# Copy_of_Plant_Monitor.net
KiCad netlist of a schematic drawn in Altium Designer
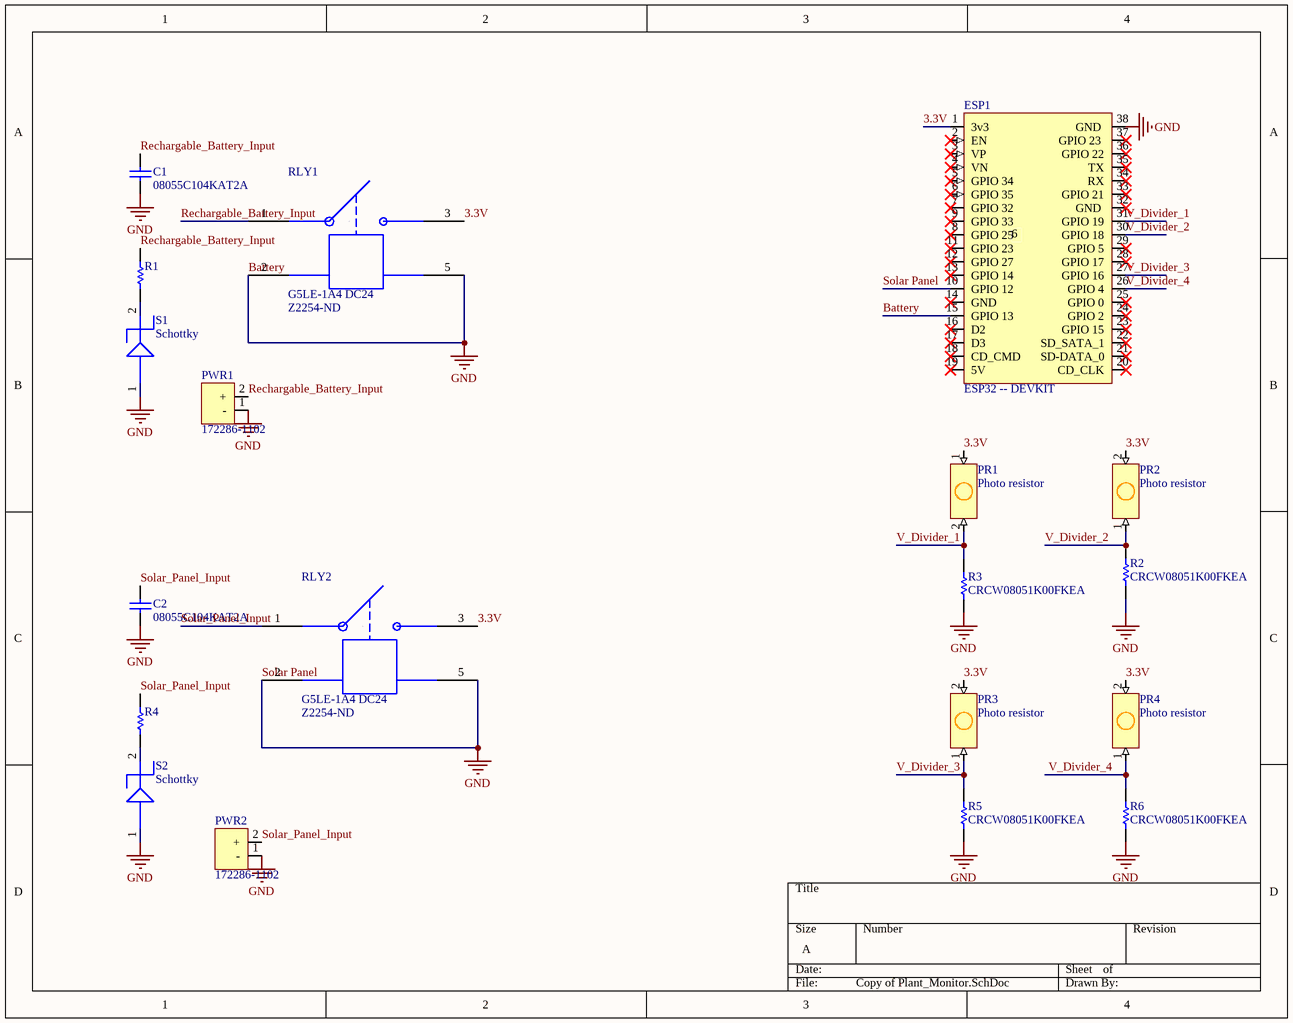
[diagram p0: Copy of Plant_Monitor.SchDoc]

(export (version "E")
  (design (tool "Eeschema 10.0.6"))
  (components
    (comp (ref "C1")
      (value "08055C104KAT2A")
      (footprint "R0805")
      (description "Chip Capacitor, Ceramic, 0.1 uF, 10%, 50 V, 0805, RoHS, Tape and Reel")
      (fields (field (name "MANUFACTURER") "AVX"))
      (libsource (lib "Schlib1") (part "CAP-NP-2"))
    )
    (comp (ref "C2")
      (value "08055C104KAT2A")
      (footprint "R0805")
      (description "Chip Capacitor, Ceramic, 0.1 uF, 10%, 50 V, 0805, RoHS, Tape and Reel")
      (fields (field (name "MANUFACTURER") "AVX"))
      (libsource (lib "Schlib1") (part "CAP-NP-2"))
    )
    (comp (ref "ESP1")
      (value "ESP32 -- DEVKIT")
      (footprint "ESP32 -- DEVKITC")
      (libsource (lib "Schlib1") (part "ESP32 -- DEVKIT"))
    )
    (comp (ref "PR1")
      (value "Photo resistor")
      (footprint "Photoresistor")
      (libsource (lib "Schlib1") (part "Photo resistor"))
    )
    (comp (ref "PR2")
      (value "Photo resistor")
      (footprint "Photoresistor")
      (libsource (lib "") (part "Photo resistor_1"))
    )
    (comp (ref "PR3")
      (value "Photo resistor")
      (footprint "Photoresistor")
      (libsource (lib "") (part "Photo resistor_1"))
    )
    (comp (ref "PR4")
      (value "Photo resistor")
      (footprint "Photoresistor")
      (libsource (lib "") (part "Photo resistor_1"))
    )
    (comp (ref "PWR1")
      (value "172286-1102")
      (footprint "2x1")
      (description "MOLEX - 172286-1102. - CONNECTOR, HEADER, 2POS, 1ROW, 3.5MM")
      (libsource (lib "Schlib1") (part "2 Pin Connector"))
    )
    (comp (ref "PWR2")
      (value "172286-1102")
      (footprint "2x1")
      (description "MOLEX - 172286-1102. - CONNECTOR, HEADER, 2POS, 1ROW, 3.5MM")
      (libsource (lib "Schlib1") (part "2 Pin Connector"))
    )
    (comp (ref "R1")
      (value "CRCW08051K00FKEA")
      (footprint "RESC2013X50X30NL20T20")
      (fields (field (name "MANUFACTURER") "Vishay Dale"))
      (libsource (lib "Altium Content Vault") (part "RES"))
    )
    (comp (ref "R2")
      (value "CRCW08051K00FKEA")
      (footprint "RESC2013X50X30NL20T20")
      (fields (field (name "MANUFACTURER") "Vishay Dale"))
      (libsource (lib "Altium Content Vault") (part "RES"))
    )
    (comp (ref "R3")
      (value "CRCW08051K00FKEA")
      (footprint "RESC2013X50X30NL20T20")
      (fields (field (name "MANUFACTURER") "Vishay Dale"))
      (libsource (lib "Altium Content Vault") (part "RES"))
    )
    (comp (ref "R4")
      (value "CRCW08051K00FKEA")
      (footprint "RESC2013X50X30NL20T20")
      (fields (field (name "MANUFACTURER") "Vishay Dale"))
      (libsource (lib "Altium Content Vault") (part "RES"))
    )
    (comp (ref "R5")
      (value "CRCW08051K00FKEA")
      (footprint "RESC2013X50X30NL20T20")
      (fields (field (name "MANUFACTURER") "Vishay Dale"))
      (libsource (lib "Altium Content Vault") (part "RES"))
    )
    (comp (ref "R6")
      (value "CRCW08051K00FKEA")
      (footprint "RESC2013X50X30NL20T20")
      (fields (field (name "MANUFACTURER") "Vishay Dale"))
      (libsource (lib "Altium Content Vault") (part "RES"))
    )
    (comp (ref "RLY1")
      (value "G5LE-1A4 DC24")
      (footprint "24V RELAY")
      (fields (field (name "SUPPLIER PART NUMBER 1") "Z2254-ND"))
      (libsource (lib "Schlib1") (part "RELAY"))
    )
    (comp (ref "RLY2")
      (value "G5LE-1A4 DC24")
      (footprint "24V RELAY")
      (fields (field (name "SUPPLIER PART NUMBER 1") "Z2254-ND"))
      (libsource (lib "Schlib1") (part "RELAY"))
    )
    (comp (ref "S1")
      (value "Schottky")
      (footprint "SODFL100X40-2N")
      (libsource (lib "Schlib1") (part "Schottky"))
    )
    (comp (ref "S2")
      (value "Schottky")
      (footprint "SODFL100X40-2N")
      (libsource (lib "Schlib1") (part "Schottky"))
    )
  )
  (nets
    (net (code "1") (name "/3.3V") (class "Default")
      (node (ref "ESP1") (pin "1") (pinfunction "3v3_1") (pintype "power_in"))
      (node (ref "PR1") (pin "1") (pintype "input"))
      (node (ref "PR2") (pin "2") (pintype "input"))
      (node (ref "PR3") (pin "2") (pintype "input"))
      (node (ref "PR4") (pin "2") (pintype "input"))
    )
    (net (code "2") (name "/Rechargable_Battery_Input") (class "Default")
      (node (ref "C1") (pin "2") (pinfunction "2_2") (pintype "passive"))
      (node (ref "PWR1") (pin "2") (pinfunction "+_2") (pintype "power_in"))
      (node (ref "R1") (pin "2") (pinfunction "2_2") (pintype "passive"))
    )
    (net (code "3") (name "/Solar_Panel_Input") (class "Default")
      (node (ref "C2") (pin "2") (pinfunction "2_2") (pintype "passive"))
      (node (ref "PWR2") (pin "2") (pinfunction "+_2") (pintype "power_in"))
      (node (ref "R4") (pin "2") (pinfunction "2_2") (pintype "passive"))
    )
    (net (code "4") (name "/V_Divider_1") (class "Default")
      (node (ref "ESP1") (pin "31") (pinfunction "GPIO_19_31") (pintype "bidirectional"))
      (node (ref "PR1") (pin "2") (pintype "input"))
      (node (ref "R3") (pin "2") (pinfunction "2_2") (pintype "passive"))
    )
    (net (code "5") (name "/V_Divider_2") (class "Default")
      (node (ref "ESP1") (pin "30") (pinfunction "GPIO_18_30") (pintype "bidirectional"))
      (node (ref "PR2") (pin "1") (pintype "input"))
      (node (ref "R2") (pin "2") (pinfunction "2_2") (pintype "passive"))
    )
    (net (code "6") (name "/V_Divider_3") (class "Default")
      (node (ref "ESP1") (pin "27") (pinfunction "GPIO_16_27") (pintype "bidirectional"))
      (node (ref "PR3") (pin "1") (pintype "input"))
      (node (ref "R5") (pin "2") (pinfunction "2_2") (pintype "passive"))
    )
    (net (code "7") (name "/V_Divider_4") (class "Default")
      (node (ref "ESP1") (pin "26") (pinfunction "GPIO_4_26") (pintype "bidirectional"))
      (node (ref "PR4") (pin "1") (pintype "input"))
      (node (ref "R6") (pin "2") (pinfunction "2_2") (pintype "passive"))
    )
    (net (code "8") (name "GND") (class "Default")
      (node (ref "C1") (pin "1") (pinfunction "1_1") (pintype "passive"))
      (node (ref "C2") (pin "1") (pinfunction "1_1") (pintype "passive"))
      (node (ref "ESP1") (pin "10") (pinfunction "GPIO_12_10") (pintype "bidirectional"))
      (node (ref "ESP1") (pin "15") (pinfunction "GPIO_13_15") (pintype "bidirectional"))
      (node (ref "ESP1") (pin "38") (pinfunction "GND_38") (pintype "power_in"))
      (node (ref "PWR1") (pin "1") (pinfunction "-_1") (pintype "power_in"))
      (node (ref "PWR2") (pin "1") (pinfunction "-_1") (pintype "power_in"))
      (node (ref "R2") (pin "1") (pinfunction "1_1") (pintype "passive"))
      (node (ref "R3") (pin "1") (pinfunction "1_1") (pintype "passive"))
      (node (ref "R5") (pin "1") (pinfunction "1_1") (pintype "passive"))
      (node (ref "R6") (pin "1") (pinfunction "1_1") (pintype "passive"))
      (node (ref "S1") (pin "1") (pintype "passive"))
      (node (ref "S2") (pin "1") (pintype "passive"))
    )
    (net (code "9") (name "Net-(R1-Pad1)") (class "Default")
      (node (ref "R1") (pin "1") (pinfunction "1_1") (pintype "passive"))
      (node (ref "S1") (pin "2") (pintype "passive"))
    )
    (net (code "10") (name "Net-(R4-Pad1)") (class "Default")
      (node (ref "R4") (pin "1") (pinfunction "1_1") (pintype "passive"))
      (node (ref "S2") (pin "2") (pintype "passive"))
    )
    (net (code "11") (name "unconnected-(ESP1-5V-Pad19)") (class "Default")
      (node (ref "ESP1") (pin "19") (pinfunction "5V_19") (pintype "power_in+no_connect"))
    )
    (net (code "12") (name "unconnected-(ESP1-CD_CLK-Pad20)") (class "Default")
      (node (ref "ESP1") (pin "20") (pinfunction "CD_CLK_20") (pintype "bidirectional+no_connect"))
    )
    (net (code "13") (name "unconnected-(ESP1-CD_CMD-Pad18)") (class "Default")
      (node (ref "ESP1") (pin "18") (pinfunction "CD_CMD_18") (pintype "bidirectional+no_connect"))
    )
    (net (code "14") (name "unconnected-(ESP1-D2-Pad16)") (class "Default")
      (node (ref "ESP1") (pin "16") (pinfunction "D2_16") (pintype "bidirectional+no_connect"))
    )
    (net (code "15") (name "unconnected-(ESP1-D3-Pad17)") (class "Default")
      (node (ref "ESP1") (pin "17") (pinfunction "D3_17") (pintype "bidirectional+no_connect"))
    )
    (net (code "16") (name "unconnected-(ESP1-EN-Pad2)") (class "Default")
      (node (ref "ESP1") (pin "2") (pinfunction "EN_2") (pintype "input+no_connect"))
    )
    (net (code "17") (name "unconnected-(ESP1-GND-Pad14)") (class "Default")
      (node (ref "ESP1") (pin "14") (pinfunction "GND_14") (pintype "power_in+no_connect"))
    )
    (net (code "18") (name "unconnected-(ESP1-GND-Pad32)") (class "Default")
      (node (ref "ESP1") (pin "32") (pinfunction "GND_32") (pintype "power_in+no_connect"))
    )
    (net (code "19") (name "unconnected-(ESP1-GPIO_0-Pad25)") (class "Default")
      (node (ref "ESP1") (pin "25") (pinfunction "GPIO_0_25") (pintype "bidirectional+no_connect"))
    )
    (net (code "20") (name "unconnected-(ESP1-GPIO_2-Pad24)") (class "Default")
      (node (ref "ESP1") (pin "24") (pinfunction "GPIO_2_24") (pintype "bidirectional+no_connect"))
    )
    (net (code "21") (name "unconnected-(ESP1-GPIO_5-Pad29)") (class "Default")
      (node (ref "ESP1") (pin "29") (pinfunction "GPIO_5_29") (pintype "bidirectional+no_connect"))
    )
    (net (code "22") (name "unconnected-(ESP1-GPIO_14-Pad13)") (class "Default")
      (node (ref "ESP1") (pin "13") (pinfunction "GPIO_14_13") (pintype "bidirectional+no_connect"))
    )
    (net (code "23") (name "unconnected-(ESP1-GPIO_15-Pad23)") (class "Default")
      (node (ref "ESP1") (pin "23") (pinfunction "GPIO_15_23") (pintype "bidirectional+no_connect"))
    )
    (net (code "24") (name "unconnected-(ESP1-GPIO_17-Pad28)") (class "Default")
      (node (ref "ESP1") (pin "28") (pinfunction "GPIO_17_28") (pintype "bidirectional+no_connect"))
    )
    (net (code "25") (name "unconnected-(ESP1-GPIO_21-Pad33)") (class "Default")
      (node (ref "ESP1") (pin "33") (pinfunction "GPIO_21_33") (pintype "bidirectional+no_connect"))
    )
    (net (code "26") (name "unconnected-(ESP1-GPIO_22-Pad36)") (class "Default")
      (node (ref "ESP1") (pin "36") (pinfunction "GPIO_22_36") (pintype "bidirectional+no_connect"))
    )
    (net (code "27") (name "unconnected-(ESP1-GPIO_23-Pad11)") (class "Default")
      (node (ref "ESP1") (pin "11") (pinfunction "GPIO_23_11") (pintype "bidirectional+no_connect"))
    )
    (net (code "28") (name "unconnected-(ESP1-GPIO_23-Pad37)") (class "Default")
      (node (ref "ESP1") (pin "37") (pinfunction "GPIO_23_37") (pintype "bidirectional+no_connect"))
    )
    (net (code "29") (name "unconnected-(ESP1-GPIO_25-Pad8)") (class "Default")
      (node (ref "ESP1") (pin "8") (pinfunction "GPIO_25_8") (pintype "bidirectional+no_connect"))
    )
    (net (code "30") (name "unconnected-(ESP1-GPIO_27-Pad12)") (class "Default")
      (node (ref "ESP1") (pin "12") (pinfunction "GPIO_27_12") (pintype "bidirectional+no_connect"))
    )
    (net (code "31") (name "unconnected-(ESP1-GPIO_32-Pad7)") (class "Default")
      (node (ref "ESP1") (pin "7") (pinfunction "GPIO_32_7") (pintype "bidirectional+no_connect"))
    )
    (net (code "32") (name "unconnected-(ESP1-GPIO_33-Pad9)") (class "Default")
      (node (ref "ESP1") (pin "9") (pinfunction "GPIO_33_9") (pintype "bidirectional+no_connect"))
    )
    (net (code "33") (name "unconnected-(ESP1-GPIO_34-Pad5)") (class "Default")
      (node (ref "ESP1") (pin "5") (pinfunction "GPIO_34_5") (pintype "input+no_connect"))
    )
    (net (code "34") (name "unconnected-(ESP1-GPIO_35-Pad6)") (class "Default")
      (node (ref "ESP1") (pin "6") (pinfunction "GPIO_35_6") (pintype "input+no_connect"))
    )
    (net (code "35") (name "unconnected-(ESP1-RX-Pad34)") (class "Default")
      (node (ref "ESP1") (pin "34") (pinfunction "RX_34") (pintype "bidirectional+no_connect"))
    )
    (net (code "36") (name "unconnected-(ESP1-SD-DATA_0-Pad21)") (class "Default")
      (node (ref "ESP1") (pin "21") (pinfunction "SD-DATA_0_21") (pintype "bidirectional+no_connect"))
    )
    (net (code "37") (name "unconnected-(ESP1-SD_SATA_1-Pad22)") (class "Default")
      (node (ref "ESP1") (pin "22") (pinfunction "SD_SATA_1_22") (pintype "bidirectional+no_connect"))
    )
    (net (code "38") (name "unconnected-(ESP1-TX-Pad35)") (class "Default")
      (node (ref "ESP1") (pin "35") (pinfunction "TX_35") (pintype "bidirectional+no_connect"))
    )
    (net (code "39") (name "unconnected-(ESP1-VN-Pad4)") (class "Default")
      (node (ref "ESP1") (pin "4") (pinfunction "VN_4") (pintype "input+no_connect"))
    )
    (net (code "40") (name "unconnected-(ESP1-VP-Pad3)") (class "Default")
      (node (ref "ESP1") (pin "3") (pinfunction "VP_3") (pintype "input+no_connect"))
    )
    (net (code "41") (name "unconnected-(RLY1-0-Pad1)") (class "Default")
      (node (ref "RLY1") (pin "1") (pinfunction "0_1") (pintype "passive"))
    )
    (net (code "42") (name "unconnected-(RLY1-1-Pad2)") (class "Default")
      (node (ref "RLY1") (pin "2") (pinfunction "1_2") (pintype "passive"))
    )
    (net (code "43") (name "unconnected-(RLY1-2-Pad3)") (class "Default")
      (node (ref "RLY1") (pin "3") (pinfunction "2_3") (pintype "passive"))
    )
    (net (code "44") (name "unconnected-(RLY1-3-Pad5)") (class "Default")
      (node (ref "RLY1") (pin "5") (pinfunction "3_5") (pintype "passive"))
    )
    (net (code "45") (name "unconnected-(RLY2-0-Pad1)") (class "Default")
      (node (ref "RLY2") (pin "1") (pinfunction "0_1") (pintype "passive"))
    )
    (net (code "46") (name "unconnected-(RLY2-1-Pad2)") (class "Default")
      (node (ref "RLY2") (pin "2") (pinfunction "1_2") (pintype "passive"))
    )
    (net (code "47") (name "unconnected-(RLY2-2-Pad3)") (class "Default")
      (node (ref "RLY2") (pin "3") (pinfunction "2_3") (pintype "passive"))
    )
    (net (code "48") (name "unconnected-(RLY2-3-Pad5)") (class "Default")
      (node (ref "RLY2") (pin "5") (pinfunction "3_5") (pintype "passive"))
    )
  )
)
